# ESP32_RC_MOD_V1.net
KiCad netlist of a schematic drawn in Altium Designer
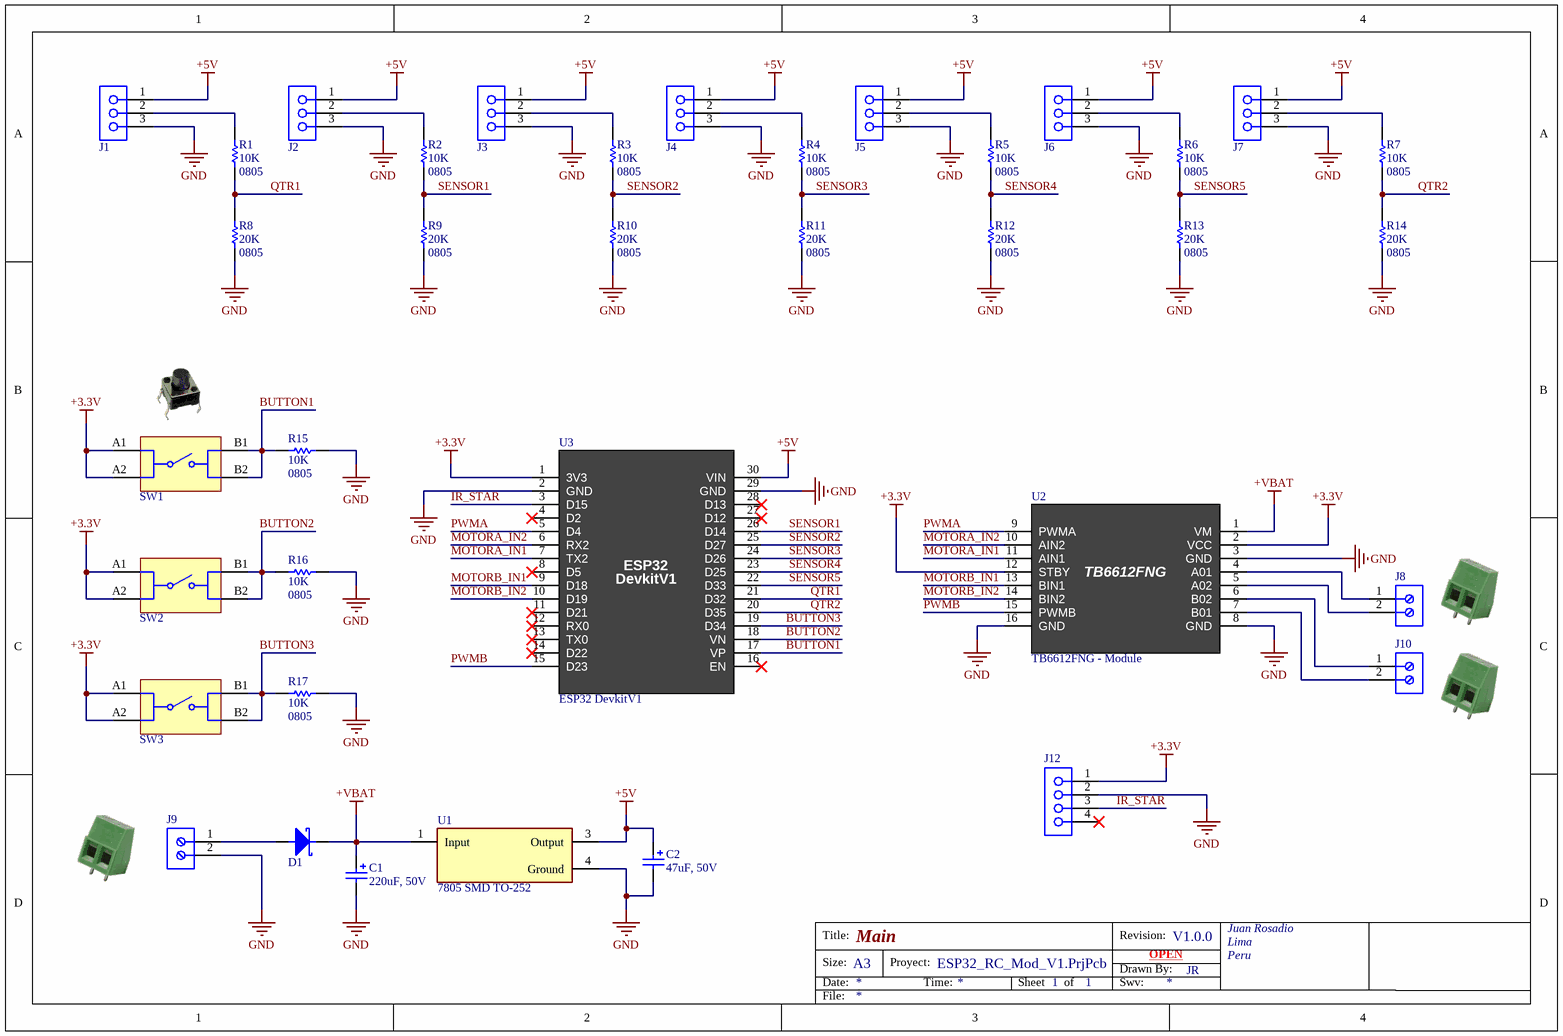
[diagram p0: ESP32_RC_MOD_V1.SchDoc]

(export (version "E")
  (design (tool "Eeschema 10.0.6"))
  (components
    (comp (ref "C1")
      (value "220uF, 50V")
      (footprint "WCAP-ATG8_D10H12.5")
      (description "WCAP-ATG8 Aluminum Electrolytic Capacitor, Radial, THT, D10xH12.5, 220uF, 50V")
      (fields
        (field (name "MANUFACTURER PART NUMBER") "860010675018")
        (field (name "MANUFACTURER") "Wurth Elektronik")
      )
      (libsource (lib "WCAP-ATG8 Aluminion Electrolytic Capacitors") (part "860010675018"))
    )
    (comp (ref "C2")
      (value "47uF, 50V")
      (footprint "WCAP-ATG8_D6.3H11")
      (description "WCAP-ATG8 Aluminum Electrolytic Capacitor, Radial, THT, D6.3xH11, 47uF, 50V")
      (fields
        (field (name "MANUFACTURER PART NUMBER") "860010673012")
        (field (name "MANUFACTURER") "Wurth Elektronik")
      )
      (libsource (lib "WCAP-ATG8 Aluminion Electrolytic Capacitors") (part "860010673012"))
    )
    (comp (ref "D1")
      (value "Diode Schottky")
      (footprint "DO-214AB")
      (description "Diodo Schottky SS36 3A 60 V")
      (libsource (lib "Diodos") (part "Diode Schottky"))
    )
    (comp (ref "J1")
      (value "Header 3P")
      (footprint "61300311821")
      (description "WR-PHD Socket Header, THT, Vertical, pitch 2.54mm, 1 Row, 3P")
      (fields
        (field (name "MANUFACTURER PART NUMBER") "61300311821")
        (field (name "MANUFACTURER") "Wurth Elektronik")
      )
      (libsource (lib "WR-PHD (rev24a)") (part "61300311821"))
    )
    (comp (ref "J2")
      (value "Header 3P")
      (footprint "61300311821")
      (description "WR-PHD Socket Header, THT, Vertical, pitch 2.54mm, 1 Row, 3P")
      (fields
        (field (name "MANUFACTURER PART NUMBER") "61300311821")
        (field (name "MANUFACTURER") "Wurth Elektronik")
      )
      (libsource (lib "WR-PHD (rev24a)") (part "61300311821"))
    )
    (comp (ref "J3")
      (value "Header 3P")
      (footprint "61300311821")
      (description "WR-PHD Socket Header, THT, Vertical, pitch 2.54mm, 1 Row, 3P")
      (fields
        (field (name "MANUFACTURER PART NUMBER") "61300311821")
        (field (name "MANUFACTURER") "Wurth Elektronik")
      )
      (libsource (lib "WR-PHD (rev24a)") (part "61300311821"))
    )
    (comp (ref "J4")
      (value "Header 3P")
      (footprint "61300311821")
      (description "WR-PHD Socket Header, THT, Vertical, pitch 2.54mm, 1 Row, 3P")
      (fields
        (field (name "MANUFACTURER PART NUMBER") "61300311821")
        (field (name "MANUFACTURER") "Wurth Elektronik")
      )
      (libsource (lib "WR-PHD (rev24a)") (part "61300311821"))
    )
    (comp (ref "J5")
      (value "Header 3P")
      (footprint "61300311821")
      (description "WR-PHD Socket Header, THT, Vertical, pitch 2.54mm, 1 Row, 3P")
      (fields
        (field (name "MANUFACTURER PART NUMBER") "61300311821")
        (field (name "MANUFACTURER") "Wurth Elektronik")
      )
      (libsource (lib "WR-PHD (rev24a)") (part "61300311821"))
    )
    (comp (ref "J6")
      (value "Header 3P")
      (footprint "61300311821")
      (description "WR-PHD Socket Header, THT, Vertical, pitch 2.54mm, 1 Row, 3P")
      (fields
        (field (name "MANUFACTURER PART NUMBER") "61300311821")
        (field (name "MANUFACTURER") "Wurth Elektronik")
      )
      (libsource (lib "WR-PHD (rev24a)") (part "61300311821"))
    )
    (comp (ref "J7")
      (value "Header 3P")
      (footprint "61300311821")
      (description "WR-PHD Socket Header, THT, Vertical, pitch 2.54mm, 1 Row, 3P")
      (fields
        (field (name "MANUFACTURER PART NUMBER") "61300311821")
        (field (name "MANUFACTURER") "Wurth Elektronik")
      )
      (libsource (lib "WR-PHD (rev24a)") (part "61300311821"))
    )
    (comp (ref "J8")
      (value "Bornera de 2 pines")
      (footprint "691111710002")
      (description "WR-TBL Serie 111 Horizontal Entry Modular, Pressure Clamp, THT, pitch 5mm, 2p")
      (fields
        (field (name "MANUFACTURER PART NUMBER") "691111710002")
        (field (name "MANUFACTURER") "Wurth Elektronik")
      )
      (libsource (lib "WR-TBL Terminal Blocks") (part "691111710002"))
    )
    (comp (ref "J9")
      (value "Bornera de 2 pines")
      (footprint "691111710002")
      (description "WR-TBL Serie 111 Horizontal Entry Modular, Pressure Clamp, THT, pitch 5mm, 2p")
      (fields
        (field (name "MANUFACTURER PART NUMBER") "691111710002")
        (field (name "MANUFACTURER") "Wurth Elektronik")
      )
      (libsource (lib "WR-TBL Terminal Blocks") (part "691111710002"))
    )
    (comp (ref "J10")
      (value "Bornera de 2 pines")
      (footprint "691111710002")
      (description "WR-TBL Serie 111 Horizontal Entry Modular, Pressure Clamp, THT, pitch 5mm, 2p")
      (fields
        (field (name "MANUFACTURER PART NUMBER") "691111710002")
        (field (name "MANUFACTURER") "Wurth Elektronik")
      )
      (libsource (lib "WR-TBL Terminal Blocks") (part "691111710002"))
    )
    (comp (ref "J12")
      (value "Header 4p")
      (footprint "61300411821")
      (description "WR-PHD Socket Header, THT, pitch 2.54mm, Single Row, Vertical, 4p")
      (fields
        (field (name "MANUFACTURER PART NUMBER") "61300411821")
        (field (name "MANUFACTURER") "Wurth Elektronik")
      )
      (libsource (lib "WE-WR PHD Conectors") (part "61300411821"))
    )
    (comp (ref "R1")
      (value "Resistor 0805")
      (footprint "RES0805A")
      (description "SMD 0805 10Kohms")
      (fields
        (field (name "TOLERANCE") "1%")
        (field (name "RESISTANCE") "10K")
        (field (name "CASE/PACKAGE") "0805")
      )
      (libsource (lib "Resistencias SMD") (part "Resistor 0805"))
    )
    (comp (ref "R2")
      (value "Resistor 0805")
      (footprint "RES0805A")
      (description "SMD 0805 10Kohms")
      (fields
        (field (name "TOLERANCE") "1%")
        (field (name "RESISTANCE") "10K")
        (field (name "CASE/PACKAGE") "0805")
      )
      (libsource (lib "Resistencias SMD") (part "Resistor 0805"))
    )
    (comp (ref "R3")
      (value "Resistor 0805")
      (footprint "RES0805A")
      (description "SMD 0805 10Kohms")
      (fields
        (field (name "TOLERANCE") "1%")
        (field (name "RESISTANCE") "10K")
        (field (name "CASE/PACKAGE") "0805")
      )
      (libsource (lib "Resistencias SMD") (part "Resistor 0805"))
    )
    (comp (ref "R4")
      (value "Resistor 0805")
      (footprint "RES0805A")
      (description "SMD 0805 10Kohms")
      (fields
        (field (name "TOLERANCE") "1%")
        (field (name "RESISTANCE") "10K")
        (field (name "CASE/PACKAGE") "0805")
      )
      (libsource (lib "Resistencias SMD") (part "Resistor 0805"))
    )
    (comp (ref "R5")
      (value "Resistor 0805")
      (footprint "RES0805A")
      (description "SMD 0805 10Kohms")
      (fields
        (field (name "TOLERANCE") "1%")
        (field (name "RESISTANCE") "10K")
        (field (name "CASE/PACKAGE") "0805")
      )
      (libsource (lib "Resistencias SMD") (part "Resistor 0805"))
    )
    (comp (ref "R6")
      (value "Resistor 0805")
      (footprint "RES0805A")
      (description "SMD 0805 10Kohms")
      (fields
        (field (name "TOLERANCE") "1%")
        (field (name "RESISTANCE") "10K")
        (field (name "CASE/PACKAGE") "0805")
      )
      (libsource (lib "Resistencias SMD") (part "Resistor 0805"))
    )
    (comp (ref "R7")
      (value "Resistor 0805")
      (footprint "RES0805A")
      (description "SMD 0805 10Kohms")
      (fields
        (field (name "TOLERANCE") "1%")
        (field (name "RESISTANCE") "10K")
        (field (name "CASE/PACKAGE") "0805")
      )
      (libsource (lib "Resistencias SMD") (part "Resistor 0805"))
    )
    (comp (ref "R8")
      (value "Resistor 0805")
      (footprint "RES0805A")
      (description "SMD 0805 20Kohms")
      (fields
        (field (name "TOLERANCE") "1%")
        (field (name "RESISTANCE") "20K")
        (field (name "CASE/PACKAGE") "0805")
      )
      (libsource (lib "Resistencias SMD") (part "Resistor 0805"))
    )
    (comp (ref "R9")
      (value "Resistor 0805")
      (footprint "RES0805A")
      (description "SMD 0805 20Kohms")
      (fields
        (field (name "TOLERANCE") "1%")
        (field (name "RESISTANCE") "20K")
        (field (name "CASE/PACKAGE") "0805")
      )
      (libsource (lib "Resistencias SMD") (part "Resistor 0805"))
    )
    (comp (ref "R10")
      (value "Resistor 0805")
      (footprint "RES0805A")
      (description "SMD 0805 20Kohms")
      (fields
        (field (name "TOLERANCE") "1%")
        (field (name "RESISTANCE") "20K")
        (field (name "CASE/PACKAGE") "0805")
      )
      (libsource (lib "Resistencias SMD") (part "Resistor 0805"))
    )
    (comp (ref "R11")
      (value "Resistor 0805")
      (footprint "RES0805A")
      (description "SMD 0805 20Kohms")
      (fields
        (field (name "TOLERANCE") "1%")
        (field (name "RESISTANCE") "20K")
        (field (name "CASE/PACKAGE") "0805")
      )
      (libsource (lib "Resistencias SMD") (part "Resistor 0805"))
    )
    (comp (ref "R12")
      (value "Resistor 0805")
      (footprint "RES0805A")
      (description "SMD 0805 20Kohms")
      (fields
        (field (name "TOLERANCE") "1%")
        (field (name "RESISTANCE") "20K")
        (field (name "CASE/PACKAGE") "0805")
      )
      (libsource (lib "Resistencias SMD") (part "Resistor 0805"))
    )
    (comp (ref "R13")
      (value "Resistor 0805")
      (footprint "RES0805A")
      (description "SMD 0805 20Kohms")
      (fields
        (field (name "TOLERANCE") "1%")
        (field (name "RESISTANCE") "20K")
        (field (name "CASE/PACKAGE") "0805")
      )
      (libsource (lib "Resistencias SMD") (part "Resistor 0805"))
    )
    (comp (ref "R14")
      (value "Resistor 0805")
      (footprint "RES0805A")
      (description "SMD 0805 20Kohms")
      (fields
        (field (name "TOLERANCE") "1%")
        (field (name "RESISTANCE") "20K")
        (field (name "CASE/PACKAGE") "0805")
      )
      (libsource (lib "Resistencias SMD") (part "Resistor 0805"))
    )
    (comp (ref "R15")
      (value "Resistor 0805")
      (footprint "RES0805A")
      (description "SMD 0805 10Kohms")
      (fields
        (field (name "TOLERANCE") "1%")
        (field (name "RESISTANCE") "10K")
        (field (name "CASE/PACKAGE") "0805")
      )
      (libsource (lib "Resistencias SMD") (part "Resistor 0805"))
    )
    (comp (ref "R16")
      (value "Resistor 0805")
      (footprint "RES0805A")
      (description "SMD 0805 10Kohms")
      (fields
        (field (name "TOLERANCE") "1%")
        (field (name "RESISTANCE") "10K")
        (field (name "CASE/PACKAGE") "0805")
      )
      (libsource (lib "Resistencias SMD") (part "Resistor 0805"))
    )
    (comp (ref "R17")
      (value "Resistor 0805")
      (footprint "RES0805A")
      (description "SMD 0805 10Kohms")
      (fields
        (field (name "TOLERANCE") "1%")
        (field (name "RESISTANCE") "10K")
        (field (name "CASE/PACKAGE") "0805")
      )
      (libsource (lib "Resistencias SMD") (part "Resistor 0805"))
    )
    (comp (ref "SW1")
      (value "XUNPU TS-1002S-07026C")
      (footprint "4301x60707x6")
      (description "6mm 7mm Round Button 50mA Brick nogging 6mm SPST 12V SMD,6x6mm Tactile Switches ROHS")
      (fields
        (field (name "MANUFACTURER PART NUMBER") "TS-1002S-07026C")
        (field (name "MANUFACTURER") "XUNPU")
      )
      (libsource (lib "WS-TATV (rev22a)") (part "430156070726"))
    )
    (comp (ref "SW2")
      (value "XUNPU TS-1002S-07026C")
      (footprint "4301x60707x6")
      (description "6mm 7mm Round Button 50mA Brick nogging 6mm SPST 12V SMD,6x6mm Tactile Switches ROHS")
      (fields
        (field (name "MANUFACTURER PART NUMBER") "TS-1002S-07026C")
        (field (name "MANUFACTURER") "XUNPU")
      )
      (libsource (lib "WS-TATV (rev22a)") (part "430156070726"))
    )
    (comp (ref "SW3")
      (value "XUNPU TS-1002S-07026C")
      (footprint "4301x60707x6")
      (description "6mm 7mm Round Button 50mA Brick nogging 6mm SPST 12V SMD,6x6mm Tactile Switches ROHS")
      (fields
        (field (name "MANUFACTURER PART NUMBER") "TS-1002S-07026C")
        (field (name "MANUFACTURER") "XUNPU")
      )
      (libsource (lib "WS-TATV (rev22a)") (part "430156070726"))
    )
    (comp (ref "U1")
      (value "7805 SMD TO-252")
      (footprint "FP-369C-MFG")
      (description "IC REG LINEAR 5V 1A DPAK")
      (fields
        (field (name "OCTOPART") "https://octopart.com/mc7805cdtg-on+semiconductor-1266408")
        (field (name "MANUFACTURER") "ON Semiconductor")
      )
      (libsource (lib "Altium Content Vault") (part "11a2526e58ef238c9de1a88af04e31c"))
    )
    (comp (ref "U2")
      (value "TB6612FNG - Module")
      (footprint "TB6612FNG-HDR-3D")
      (description "Driver Puente H TB6612FNG 1.2A")
      (libsource (lib "Modulos") (part "TB6612FNG - Module"))
    )
    (comp (ref "U3")
      (value "ESP32 DevkitV1")
      (footprint "ESP32 DEVKITV1 - HDR - 3D")
      (description "ESP32 DEVKIT V1 Wireless WiFi Bluetooth Placa de desarrollo Micro USB Dual Core")
      (libsource (lib "Modulos") (part "ESP32 DevkitV1"))
    )
  )
  (nets
    (net (code "1") (name "+3.3V") (class "Default")
      (node (ref "J12") (pin "1") (pinfunction "1_1") (pintype "passive"))
      (node (ref "SW1") (pin "A1") (pinfunction "A1_A1") (pintype "passive"))
      (node (ref "SW1") (pin "A2") (pinfunction "A2_A2") (pintype "passive"))
      (node (ref "SW2") (pin "A1") (pinfunction "A1_A1") (pintype "passive"))
      (node (ref "SW2") (pin "A2") (pinfunction "A2_A2") (pintype "passive"))
      (node (ref "SW3") (pin "A1") (pinfunction "A1_A1") (pintype "passive"))
      (node (ref "SW3") (pin "A2") (pinfunction "A2_A2") (pintype "passive"))
      (node (ref "U2") (pin "12") (pinfunction "STBY_12") (pintype "passive"))
      (node (ref "U2") (pin "2") (pinfunction "VCC_2") (pintype "passive"))
      (node (ref "U3") (pin "1") (pinfunction "3V3_1") (pintype "power_in"))
    )
    (net (code "2") (name "+5V") (class "Default")
      (node (ref "C2") (pin "1") (pinfunction "P_1") (pintype "passive"))
      (node (ref "J1") (pin "1") (pinfunction "1_1") (pintype "passive"))
      (node (ref "J2") (pin "1") (pinfunction "1_1") (pintype "passive"))
      (node (ref "J3") (pin "1") (pinfunction "1_1") (pintype "passive"))
      (node (ref "J4") (pin "1") (pinfunction "1_1") (pintype "passive"))
      (node (ref "J5") (pin "1") (pinfunction "1_1") (pintype "passive"))
      (node (ref "J6") (pin "1") (pinfunction "1_1") (pintype "passive"))
      (node (ref "J7") (pin "1") (pinfunction "1_1") (pintype "passive"))
      (node (ref "U1") (pin "3") (pinfunction "Output_3") (pintype "power_in"))
      (node (ref "U3") (pin "30") (pinfunction "VIN_30") (pintype "power_in"))
    )
    (net (code "3") (name "+VBAT") (class "Default")
      (node (ref "C1") (pin "1") (pinfunction "P_1") (pintype "passive"))
      (node (ref "D1") (pin "2") (pinfunction "K_2") (pintype "passive"))
      (node (ref "U1") (pin "1") (pinfunction "Input_1") (pintype "power_in"))
      (node (ref "U2") (pin "1") (pinfunction "VM_1") (pintype "power_in"))
    )
    (net (code "4") (name "/BUTTON1") (class "Default")
      (node (ref "R15") (pin "2") (pinfunction "2_2") (pintype "passive"))
      (node (ref "SW1") (pin "B1") (pinfunction "B1_B1") (pintype "passive"))
      (node (ref "SW1") (pin "B2") (pinfunction "B2_B2") (pintype "passive"))
      (node (ref "U3") (pin "17") (pinfunction "VP_17") (pintype "passive"))
    )
    (net (code "5") (name "/BUTTON2") (class "Default")
      (node (ref "R16") (pin "2") (pinfunction "2_2") (pintype "passive"))
      (node (ref "SW2") (pin "B1") (pinfunction "B1_B1") (pintype "passive"))
      (node (ref "SW2") (pin "B2") (pinfunction "B2_B2") (pintype "passive"))
      (node (ref "U3") (pin "18") (pinfunction "VN_18") (pintype "passive"))
    )
    (net (code "6") (name "/BUTTON3") (class "Default")
      (node (ref "R17") (pin "2") (pinfunction "2_2") (pintype "passive"))
      (node (ref "SW3") (pin "B1") (pinfunction "B1_B1") (pintype "passive"))
      (node (ref "SW3") (pin "B2") (pinfunction "B2_B2") (pintype "passive"))
      (node (ref "U3") (pin "19") (pinfunction "D34_19") (pintype "passive"))
    )
    (net (code "7") (name "/IR_STAR") (class "Default")
      (node (ref "J12") (pin "3") (pinfunction "3_3") (pintype "passive"))
      (node (ref "U3") (pin "3") (pinfunction "D15_3") (pintype "passive"))
    )
    (net (code "8") (name "/MOTORA_IN1") (class "Default")
      (node (ref "U2") (pin "11") (pinfunction "AIN1_11") (pintype "passive"))
      (node (ref "U3") (pin "7") (pinfunction "TX2_7") (pintype "passive"))
    )
    (net (code "9") (name "/MOTORA_IN2") (class "Default")
      (node (ref "U2") (pin "10") (pinfunction "AIN2_10") (pintype "passive"))
      (node (ref "U3") (pin "6") (pinfunction "RX2_6") (pintype "passive"))
    )
    (net (code "10") (name "/MOTORB_IN1") (class "Default")
      (node (ref "U2") (pin "13") (pinfunction "BIN1_13") (pintype "passive"))
      (node (ref "U3") (pin "9") (pinfunction "D18_9") (pintype "passive"))
    )
    (net (code "11") (name "/MOTORB_IN2") (class "Default")
      (node (ref "U2") (pin "14") (pinfunction "BIN2_14") (pintype "passive"))
      (node (ref "U3") (pin "10") (pinfunction "D19_10") (pintype "passive"))
    )
    (net (code "12") (name "/PWMA") (class "Default")
      (node (ref "U2") (pin "9") (pinfunction "PWMA_9") (pintype "passive"))
      (node (ref "U3") (pin "5") (pinfunction "D4_5") (pintype "passive"))
    )
    (net (code "13") (name "/PWMB") (class "Default")
      (node (ref "U2") (pin "15") (pinfunction "PWMB_15") (pintype "passive"))
      (node (ref "U3") (pin "15") (pinfunction "D23_15") (pintype "passive"))
    )
    (net (code "14") (name "/QTR1") (class "Default")
      (node (ref "R1") (pin "1") (pinfunction "1_1") (pintype "passive"))
      (node (ref "R8") (pin "2") (pinfunction "2_2") (pintype "passive"))
      (node (ref "U3") (pin "21") (pinfunction "D32_21") (pintype "passive"))
    )
    (net (code "15") (name "/QTR2") (class "Default")
      (node (ref "R14") (pin "2") (pinfunction "2_2") (pintype "passive"))
      (node (ref "R7") (pin "1") (pinfunction "1_1") (pintype "passive"))
      (node (ref "U3") (pin "20") (pinfunction "D35_20") (pintype "passive"))
    )
    (net (code "16") (name "/SENSOR1") (class "Default")
      (node (ref "R2") (pin "1") (pinfunction "1_1") (pintype "passive"))
      (node (ref "R9") (pin "2") (pinfunction "2_2") (pintype "passive"))
      (node (ref "U3") (pin "26") (pinfunction "D14_26") (pintype "passive"))
    )
    (net (code "17") (name "/SENSOR2") (class "Default")
      (node (ref "R10") (pin "2") (pinfunction "2_2") (pintype "passive"))
      (node (ref "R3") (pin "1") (pinfunction "1_1") (pintype "passive"))
      (node (ref "U3") (pin "25") (pinfunction "D27_25") (pintype "passive"))
    )
    (net (code "18") (name "/SENSOR3") (class "Default")
      (node (ref "R11") (pin "2") (pinfunction "2_2") (pintype "passive"))
      (node (ref "R4") (pin "1") (pinfunction "1_1") (pintype "passive"))
      (node (ref "U3") (pin "24") (pinfunction "D26_24") (pintype "passive"))
    )
    (net (code "19") (name "/SENSOR4") (class "Default")
      (node (ref "R12") (pin "2") (pinfunction "2_2") (pintype "passive"))
      (node (ref "R5") (pin "1") (pinfunction "1_1") (pintype "passive"))
      (node (ref "U3") (pin "23") (pinfunction "D25_23") (pintype "passive"))
    )
    (net (code "20") (name "/SENSOR5") (class "Default")
      (node (ref "R13") (pin "2") (pinfunction "2_2") (pintype "passive"))
      (node (ref "R6") (pin "1") (pinfunction "1_1") (pintype "passive"))
      (node (ref "U3") (pin "22") (pinfunction "D33_22") (pintype "passive"))
    )
    (net (code "21") (name "GND") (class "Default")
      (node (ref "C1") (pin "2") (pinfunction "N_2") (pintype "passive"))
      (node (ref "C2") (pin "2") (pinfunction "N_2") (pintype "passive"))
      (node (ref "J1") (pin "3") (pinfunction "3_3") (pintype "passive"))
      (node (ref "J12") (pin "2") (pinfunction "2_2") (pintype "passive"))
      (node (ref "J2") (pin "3") (pinfunction "3_3") (pintype "passive"))
      (node (ref "J3") (pin "3") (pinfunction "3_3") (pintype "passive"))
      (node (ref "J4") (pin "3") (pinfunction "3_3") (pintype "passive"))
      (node (ref "J5") (pin "3") (pinfunction "3_3") (pintype "passive"))
      (node (ref "J6") (pin "3") (pinfunction "3_3") (pintype "passive"))
      (node (ref "J7") (pin "3") (pinfunction "3_3") (pintype "passive"))
      (node (ref "J9") (pin "2") (pinfunction "2_2") (pintype "passive"))
      (node (ref "R10") (pin "1") (pinfunction "1_1") (pintype "passive"))
      (node (ref "R11") (pin "1") (pinfunction "1_1") (pintype "passive"))
      (node (ref "R12") (pin "1") (pinfunction "1_1") (pintype "passive"))
      (node (ref "R13") (pin "1") (pinfunction "1_1") (pintype "passive"))
      (node (ref "R14") (pin "1") (pinfunction "1_1") (pintype "passive"))
      (node (ref "R15") (pin "1") (pinfunction "1_1") (pintype "passive"))
      (node (ref "R16") (pin "1") (pinfunction "1_1") (pintype "passive"))
      (node (ref "R17") (pin "1") (pinfunction "1_1") (pintype "passive"))
      (node (ref "R8") (pin "1") (pinfunction "1_1") (pintype "passive"))
      (node (ref "R9") (pin "1") (pinfunction "1_1") (pintype "passive"))
      (node (ref "U1") (pin "4") (pinfunction "Ground_4") (pintype "power_in"))
      (node (ref "U2") (pin "16") (pinfunction "GND_16") (pintype "passive"))
      (node (ref "U2") (pin "3") (pinfunction "GND_3") (pintype "passive"))
      (node (ref "U2") (pin "8") (pinfunction "GND_8") (pintype "power_in"))
      (node (ref "U3") (pin "2") (pinfunction "GND_2") (pintype "power_in"))
      (node (ref "U3") (pin "29") (pinfunction "GND_29") (pintype "power_in"))
    )
    (net (code "22") (name "Net-(D1-A)") (class "Default")
      (node (ref "D1") (pin "1") (pinfunction "A_1") (pintype "passive"))
      (node (ref "J9") (pin "1") (pinfunction "1_1") (pintype "passive"))
    )
    (net (code "23") (name "Net-(J1-Pad2)") (class "Default")
      (node (ref "J1") (pin "2") (pinfunction "2_2") (pintype "passive"))
      (node (ref "R1") (pin "2") (pinfunction "2_2") (pintype "passive"))
    )
    (net (code "24") (name "Net-(J2-Pad2)") (class "Default")
      (node (ref "J2") (pin "2") (pinfunction "2_2") (pintype "passive"))
      (node (ref "R2") (pin "2") (pinfunction "2_2") (pintype "passive"))
    )
    (net (code "25") (name "Net-(J3-Pad2)") (class "Default")
      (node (ref "J3") (pin "2") (pinfunction "2_2") (pintype "passive"))
      (node (ref "R3") (pin "2") (pinfunction "2_2") (pintype "passive"))
    )
    (net (code "26") (name "Net-(J4-Pad2)") (class "Default")
      (node (ref "J4") (pin "2") (pinfunction "2_2") (pintype "passive"))
      (node (ref "R4") (pin "2") (pinfunction "2_2") (pintype "passive"))
    )
    (net (code "27") (name "Net-(J5-Pad2)") (class "Default")
      (node (ref "J5") (pin "2") (pinfunction "2_2") (pintype "passive"))
      (node (ref "R5") (pin "2") (pinfunction "2_2") (pintype "passive"))
    )
    (net (code "28") (name "Net-(J6-Pad2)") (class "Default")
      (node (ref "J6") (pin "2") (pinfunction "2_2") (pintype "passive"))
      (node (ref "R6") (pin "2") (pinfunction "2_2") (pintype "passive"))
    )
    (net (code "29") (name "Net-(J7-Pad2)") (class "Default")
      (node (ref "J7") (pin "2") (pinfunction "2_2") (pintype "passive"))
      (node (ref "R7") (pin "2") (pinfunction "2_2") (pintype "passive"))
    )
    (net (code "30") (name "Net-(U2-A01)") (class "Default")
      (node (ref "J8") (pin "1") (pinfunction "1_1") (pintype "passive"))
      (node (ref "U2") (pin "4") (pinfunction "A01_4") (pintype "passive"))
    )
    (net (code "31") (name "Net-(U2-A02)") (class "Default")
      (node (ref "J8") (pin "2") (pinfunction "2_2") (pintype "passive"))
      (node (ref "U2") (pin "5") (pinfunction "A02_5") (pintype "power_in"))
    )
    (net (code "32") (name "Net-(U2-B01)") (class "Default")
      (node (ref "J10") (pin "2") (pinfunction "2_2") (pintype "passive"))
      (node (ref "U2") (pin "7") (pinfunction "B01_7") (pintype "power_in"))
    )
    (net (code "33") (name "Net-(U2-B02)") (class "Default")
      (node (ref "J10") (pin "1") (pinfunction "1_1") (pintype "passive"))
      (node (ref "U2") (pin "6") (pinfunction "B02_6") (pintype "power_in"))
    )
    (net (code "34") (name "unconnected-(J12-Pad4)") (class "Default")
      (node (ref "J12") (pin "4") (pinfunction "4_4") (pintype "passive+no_connect"))
    )
    (net (code "35") (name "unconnected-(U3-D2-Pad4)") (class "Default")
      (node (ref "U3") (pin "4") (pinfunction "D2_4") (pintype "passive+no_connect"))
    )
    (net (code "36") (name "unconnected-(U3-D5-Pad8)") (class "Default")
      (node (ref "U3") (pin "8") (pinfunction "D5_8") (pintype "passive+no_connect"))
    )
    (net (code "37") (name "unconnected-(U3-D12-Pad27)") (class "Default")
      (node (ref "U3") (pin "27") (pinfunction "D12_27") (pintype "passive+no_connect"))
    )
    (net (code "38") (name "unconnected-(U3-D13-Pad28)") (class "Default")
      (node (ref "U3") (pin "28") (pinfunction "D13_28") (pintype "passive+no_connect"))
    )
    (net (code "39") (name "unconnected-(U3-D21-Pad11)") (class "Default")
      (node (ref "U3") (pin "11") (pinfunction "D21_11") (pintype "passive+no_connect"))
    )
    (net (code "40") (name "unconnected-(U3-D22-Pad14)") (class "Default")
      (node (ref "U3") (pin "14") (pinfunction "D22_14") (pintype "passive+no_connect"))
    )
    (net (code "41") (name "unconnected-(U3-EN-Pad16)") (class "Default")
      (node (ref "U3") (pin "16") (pinfunction "EN_16") (pintype "passive+no_connect"))
    )
    (net (code "42") (name "unconnected-(U3-RX0-Pad12)") (class "Default")
      (node (ref "U3") (pin "12") (pinfunction "RX0_12") (pintype "passive+no_connect"))
    )
    (net (code "43") (name "unconnected-(U3-TX0-Pad13)") (class "Default")
      (node (ref "U3") (pin "13") (pinfunction "TX0_13") (pintype "passive+no_connect"))
    )
  )
)
